# input_power.net
KiCad netlist of a schematic drawn in Altium Designer
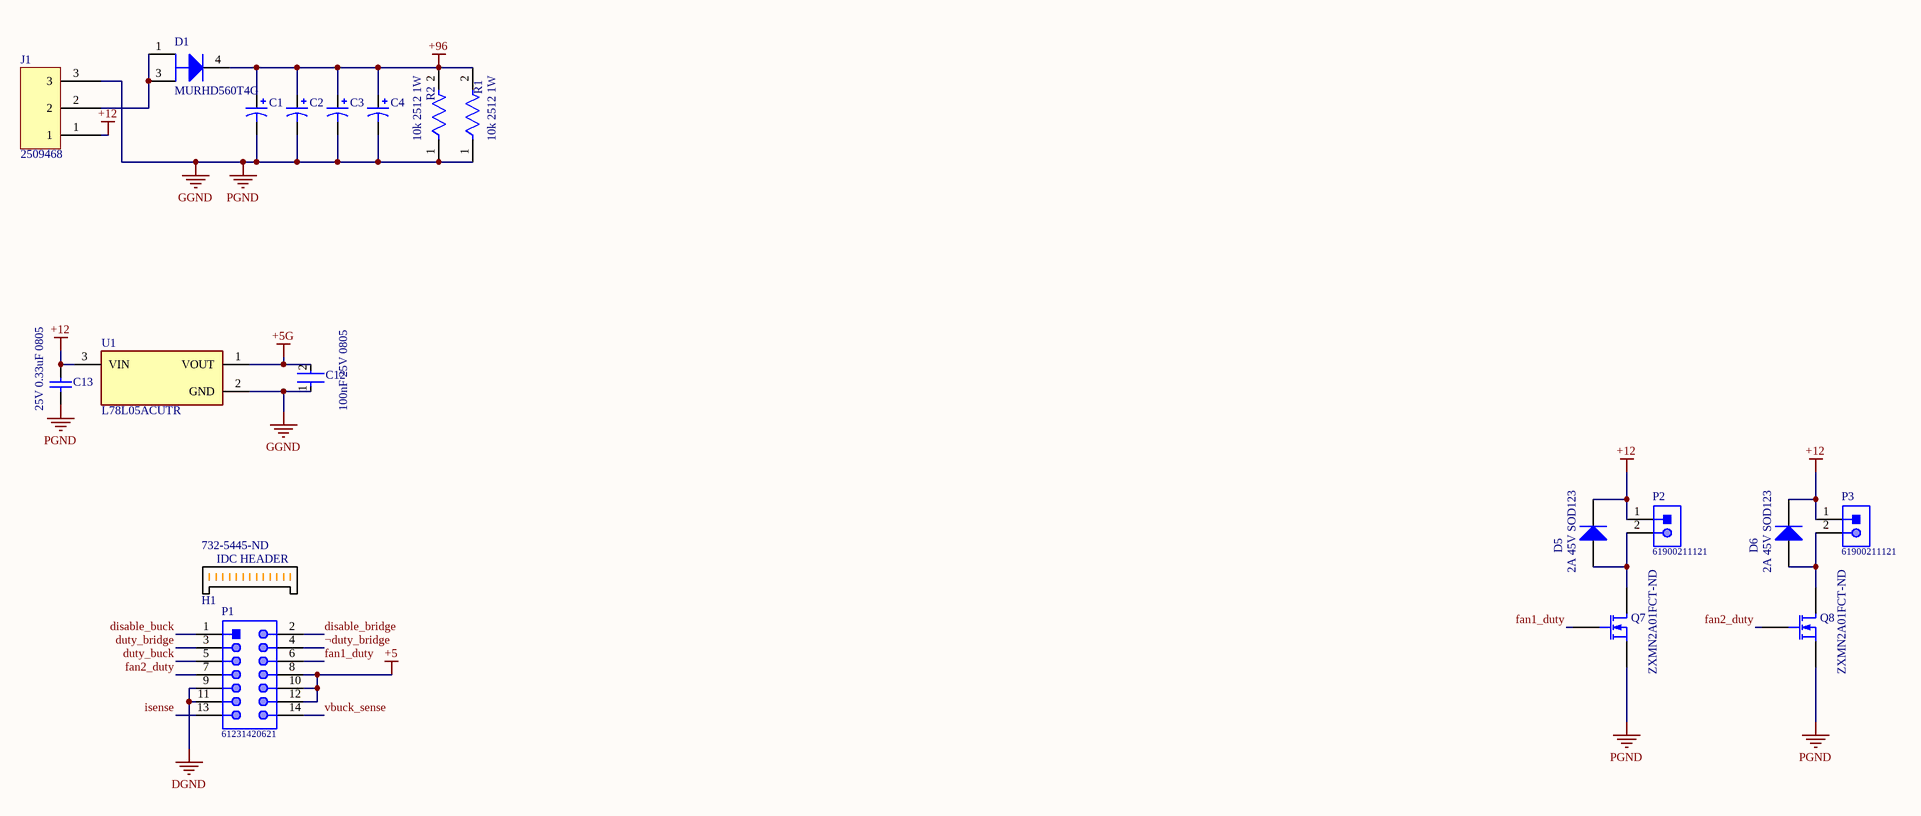
[diagram p0: input_power.SchDoc]

(export (version "E")
  (design (tool "Eeschema 10.0.6"))
  (components
    (comp (ref "C1")
      (value "560uF 80V")
      (footprint "80ZLH560MEFC18X20")
      (description "Polarized Capacitor (Radial)")
      (fields (field (name "PUBLISHER") "Altium Limited"))
      (libsource (lib "Miscellaneous Devices") (part "Cap Pol1"))
    )
    (comp (ref "C2")
      (value "560uF 80V")
      (footprint "80ZLH560MEFC18X20")
      (description "Polarized Capacitor (Radial)")
      (fields (field (name "PUBLISHER") "Altium Limited"))
      (libsource (lib "Miscellaneous Devices") (part "Cap Pol1"))
    )
    (comp (ref "C3")
      (value "560uF 80V")
      (footprint "80ZLH560MEFC18X20")
      (description "Polarized Capacitor (Radial)")
      (fields (field (name "PUBLISHER") "Altium Limited"))
      (libsource (lib "Miscellaneous Devices") (part "Cap Pol1"))
    )
    (comp (ref "C4")
      (value "560uF 80V")
      (footprint "80ZLH560MEFC18X20")
      (description "Polarized Capacitor (Radial)")
      (fields (field (name "PUBLISHER") "Altium Limited"))
      (libsource (lib "Miscellaneous Devices") (part "Cap Pol1"))
    )
    (comp (ref "C12")
      (value "100nF 25V 0805")
      (footprint "FP-CC0805-0_85-MFG")
      (description "CAP CER 0.1UF 25V X7R 0805")
      (fields (field (name "MANUFACTURER PART NUMBER") "CC0805KRX7R8BB104") (field (name "TOLERANCE") "0.1"))
      (libsource (lib "Altium Content Vault") (part "11868f565c42a9108669ba33697ecf6"))
    )
    (comp (ref "C13")
      (value "25V 0.33uF 0805")
      (footprint "CAPC2013X140X50ML20T25")
      (fields
        (field (name "PART NUMBER") "08053C334KAT2A")
        (field (name "MANUFACTURER") "AVX Interconnect / Elco")
      )
      (libsource (lib "Altium Content Vault") (part "CAP"))
    )
    (comp (ref "D1")
      (value "MURHD560T4G")
      (footprint "ONSC-DPAK-3-369C-01_V")
      (description "Power Rectifier, 3-Pin DPAK, Pb-Free, Tape and Reel")
      (fields (field (name "MANUFACTURER") "On Semiconductor"))
      (libsource (lib "Altium Content Vault") (part "ONSC-D-A1A3K4-3"))
    )
    (comp (ref "D5")
      (value "2A 45V SOD123")
      (footprint "SOD123F")
      (description "Default Diode")
      (fields (field (name "PUBLISHER") "Altium Limited"))
      (libsource (lib "Miscellaneous Devices") (part "Diode"))
    )
    (comp (ref "D6")
      (value "2A 45V SOD123")
      (footprint "SOD123F")
      (description "Default Diode")
      (fields (field (name "PUBLISHER") "Altium Limited"))
      (libsource (lib "Miscellaneous Devices") (part "Diode"))
    )
    (comp (ref "H1")
      (value "Generic IDC Header")
      (description "Assign Supplier Link Manually")
      (fields (field (name "SUPPLIER PART NUMBER 1") "732-5445-ND"))
      (libsource (lib "coil_driver_lib") (part "generic_idc_header"))
    )
    (comp (ref "J1")
      (value "weidmuller_20A_3p")
      (footprint "weidmuller_3p_20A")
      (description "3 Pin Terminal Block 19A Male Receptor")
      (fields (field (name "SUPPLIER PART NUMBER 1") "2509468"))
      (libsource (lib "coil_driver_lib") (part "weidmuller_20A_3p"))
    )
    (comp (ref "P1")
      (value "61231420621")
      (footprint "61231420621")
      (description "Male Box Header WR-BHD, SMT, Vertical, pitch 2.54 mm, 14 pins")
      (fields (field (name "MANUFACTURER") "Wurth Elektronik") (field (name "PUBLISHER") "WurthElektronik"))
      (libsource (lib "Altium Content Vault") (part "WE-CN-2P-M-R14"))
    )
    (comp (ref "P2")
      (value "61900211121")
      (footprint "61900211121")
      (description "Male Locking Header WR-WTB, THT, Vertical, pitch 2.54 mm, 1 x 2 position")
      (fields (field (name "MANUFACTURER") "Wurth Elektronik") (field (name "PUBLISHER") "WurthElektronik"))
      (libsource (lib "Altium Content Vault") (part "WE-CN-1P-M-R2"))
    )
    (comp (ref "P3")
      (value "61900211121")
      (footprint "61900211121")
      (description "Male Locking Header WR-WTB, THT, Vertical, pitch 2.54 mm, 1 x 2 position")
      (fields (field (name "MANUFACTURER") "Wurth Elektronik") (field (name "PUBLISHER") "WurthElektronik"))
      (libsource (lib "Altium Content Vault") (part "WE-CN-1P-M-R2"))
    )
    (comp (ref "Q7")
      (value "MOSFET-N")
      (footprint "DIODES SOT-23-3")
      (description "20V 120mOhm Vgs=700mV")
      (fields
        (field (name "SUPPLIER PART NUMBER 1") "ZXMN2A01FCT-ND")
        (field (name "PUBLISHER") "Altium Limited")
      )
      (libsource (lib "Miscellaneous Devices") (part "MOSFET-N"))
    )
    (comp (ref "Q8")
      (value "MOSFET-N")
      (footprint "DIODES SOT-23-3")
      (description "20V 120mOhm Vgs=700mV")
      (fields
        (field (name "SUPPLIER PART NUMBER 1") "ZXMN2A01FCT-ND")
        (field (name "PUBLISHER") "Altium Limited")
      )
      (libsource (lib "Miscellaneous Devices") (part "MOSFET-N"))
    )
    (comp (ref "R1")
      (value "10k 2512 1W")
      (footprint "FP-CRCW2512-e3-IPC_C")
      (description "RES Thick Film, 10kΩ, 5%, 1W, 200ppm/°C, 2512\r\nCRCW251210K0JNEG")
      (fields (field (name "TOLERANCE") "5%"))
      (libsource (lib "Altium Content Vault") (part "1029c3af85768c4190bb7ad29bc67b5"))
    )
    (comp (ref "R2")
      (value "10k 2512 1W")
      (footprint "FP-CRCW2512-e3-IPC_C")
      (description "RES Thick Film, 10kΩ, 5%, 1W, 200ppm/°C, 2512\r\nCRCW251210K0JNEG")
      (fields (field (name "TOLERANCE") "5%"))
      (libsource (lib "Altium Content Vault") (part "1029c3af85768c4190bb7ad29bc67b5"))
    )
    (comp (ref "U1")
      (value "L78L05ACUTR")
      (footprint "FP-SOT-89-7098166-MFG")
      (description "IC REG LINEAR 5V 100MA SOT89-3")
      (libsource (lib "Altium Content Vault") (part "ae6bee9076d4e2dbe8e374331bf90c1"))
    )
  )
  (nets
    (net (code "1") (name "+5") (class "Default")
      (node (ref "P1") (pin "10") (pinfunction "10_10") (pintype "passive"))
      (node (ref "P1") (pin "12") (pinfunction "12_12") (pintype "passive"))
      (node (ref "P1") (pin "8") (pinfunction "8_8") (pintype "passive"))
    )
    (net (code "2") (name "+5G") (class "Default")
      (node (ref "C12") (pin "2") (pinfunction "2_2") (pintype "passive"))
      (node (ref "U1") (pin "1") (pinfunction "VOUT_1") (pintype "power_in"))
    )
    (net (code "3") (name "+12") (class "Default")
      (node (ref "C13") (pin "2") (pinfunction "2_2") (pintype "passive"))
      (node (ref "D5") (pin "2") (pinfunction "K_2") (pintype "passive"))
      (node (ref "D6") (pin "2") (pinfunction "K_2") (pintype "passive"))
      (node (ref "J1") (pin "1") (pinfunction "1_1") (pintype "passive"))
      (node (ref "P2") (pin "1") (pinfunction "1_1") (pintype "passive"))
      (node (ref "P3") (pin "1") (pinfunction "1_1") (pintype "passive"))
      (node (ref "U1") (pin "3") (pinfunction "VIN_3") (pintype "power_in"))
    )
    (net (code "4") (name "+96") (class "Default")
      (node (ref "C1") (pin "1") (pinfunction "1_1") (pintype "passive"))
      (node (ref "C2") (pin "1") (pinfunction "1_1") (pintype "passive"))
      (node (ref "C3") (pin "1") (pinfunction "1_1") (pintype "passive"))
      (node (ref "C4") (pin "1") (pinfunction "1_1") (pintype "passive"))
      (node (ref "D1") (pin "4") (pinfunction "K_4") (pintype "passive"))
      (node (ref "R1") (pin "2") (pinfunction "2_2") (pintype "passive"))
      (node (ref "R2") (pin "2") (pinfunction "2_2") (pintype "passive"))
    )
    (net (code "5") (name "/disable_bridge") (class "Default")
      (node (ref "P1") (pin "2") (pinfunction "2_2") (pintype "passive"))
    )
    (net (code "6") (name "/disable_buck") (class "Default")
      (node (ref "P1") (pin "1") (pinfunction "1_1") (pintype "passive"))
    )
    (net (code "7") (name "/duty_bridge") (class "Default")
      (node (ref "P1") (pin "3") (pinfunction "3_3") (pintype "passive"))
    )
    (net (code "8") (name "/duty_buck") (class "Default")
      (node (ref "P1") (pin "5") (pinfunction "5_5") (pintype "passive"))
    )
    (net (code "9") (name "/fan1_duty") (class "Default")
      (node (ref "P1") (pin "6") (pinfunction "6_6") (pintype "passive"))
      (node (ref "Q7") (pin "2") (pinfunction "G_2") (pintype "passive"))
    )
    (net (code "10") (name "/fan2_duty") (class "Default")
      (node (ref "P1") (pin "7") (pinfunction "7_7") (pintype "passive"))
      (node (ref "Q8") (pin "2") (pinfunction "G_2") (pintype "passive"))
    )
    (net (code "11") (name "/isense") (class "Default")
      (node (ref "P1") (pin "13") (pinfunction "13_13") (pintype "passive"))
    )
    (net (code "12") (name "/vbuck_sense") (class "Default")
      (node (ref "P1") (pin "14") (pinfunction "14_14") (pintype "passive"))
    )
    (net (code "13") (name "/¬duty_bridge") (class "Default")
      (node (ref "P1") (pin "4") (pinfunction "4_4") (pintype "passive"))
    )
    (net (code "14") (name "DGND") (class "Default")
      (node (ref "P1") (pin "11") (pinfunction "11_11") (pintype "passive"))
      (node (ref "P1") (pin "9") (pinfunction "9_9") (pintype "passive"))
    )
    (net (code "15") (name "GGND") (class "Default")
      (node (ref "C1") (pin "2") (pinfunction "2_2") (pintype "passive"))
      (node (ref "C12") (pin "1") (pinfunction "1_1") (pintype "passive"))
      (node (ref "C13") (pin "1") (pinfunction "1_1") (pintype "passive"))
      (node (ref "C2") (pin "2") (pinfunction "2_2") (pintype "passive"))
      (node (ref "C3") (pin "2") (pinfunction "2_2") (pintype "passive"))
      (node (ref "C4") (pin "2") (pinfunction "2_2") (pintype "passive"))
      (node (ref "J1") (pin "3") (pinfunction "3_3") (pintype "passive"))
      (node (ref "Q7") (pin "3") (pinfunction "S_3") (pintype "passive"))
      (node (ref "Q8") (pin "3") (pinfunction "S_3") (pintype "passive"))
      (node (ref "R1") (pin "1") (pinfunction "1_1") (pintype "passive"))
      (node (ref "R2") (pin "1") (pinfunction "1_1") (pintype "passive"))
      (node (ref "U1") (pin "2") (pinfunction "GND_2") (pintype "power_in"))
    )
    (net (code "16") (name "Net-(D1-A-Pad1)") (class "Default")
      (node (ref "D1") (pin "1") (pinfunction "A_1") (pintype "passive"))
      (node (ref "D1") (pin "3") (pinfunction "A_3") (pintype "passive"))
      (node (ref "J1") (pin "2") (pinfunction "2_2") (pintype "passive"))
    )
    (net (code "17") (name "Net-(D5-A)") (class "Default")
      (node (ref "D5") (pin "1") (pinfunction "A_1") (pintype "passive"))
      (node (ref "P2") (pin "2") (pinfunction "2_2") (pintype "passive"))
      (node (ref "Q7") (pin "1") (pinfunction "D_1") (pintype "passive"))
    )
    (net (code "18") (name "Net-(D6-A)") (class "Default")
      (node (ref "D6") (pin "1") (pinfunction "A_1") (pintype "passive"))
      (node (ref "P3") (pin "2") (pinfunction "2_2") (pintype "passive"))
      (node (ref "Q8") (pin "1") (pinfunction "D_1") (pintype "passive"))
    )
  )
)
